# Battery.net
KiCad netlist of a schematic drawn in Altium Designer
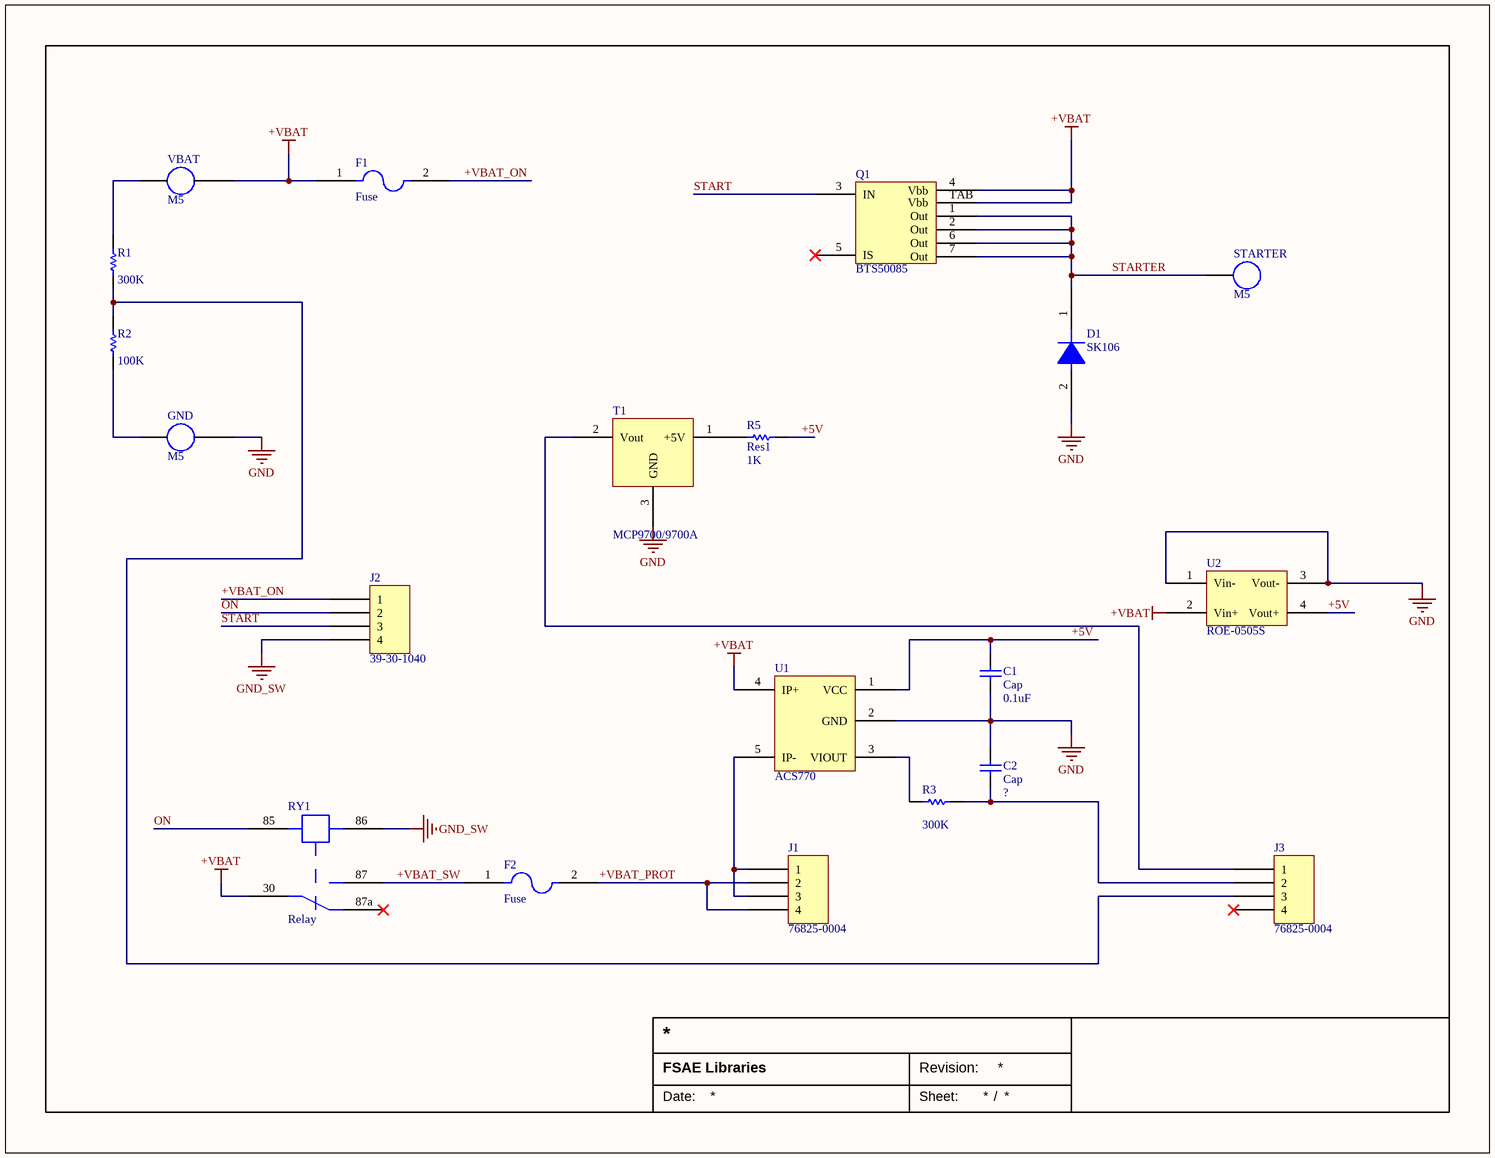
[diagram p0: Battery.SchDoc]

(export (version "E")
  (design (tool "Eeschema 10.0.6"))
  (components
    (comp (ref "C1")
      (value "Cap")
      (footprint "RAD-0.3")
      (description "Capacitor")
      (fields (field (name "ALTIUM_VALUE") "0.1uF") (field (name "PUBLISHER") "Altium Limited"))
      (libsource (lib "Miscellaneous Devices") (part "Cap"))
    )
    (comp (ref "C2")
      (value "Cap")
      (footprint "RAD-0.3")
      (description "Capacitor")
      (fields (field (name "ALTIUM_VALUE") "?") (field (name "PUBLISHER") "Altium Limited"))
      (libsource (lib "Miscellaneous Devices") (part "Cap"))
    )
    (comp (ref "D1") (value "SK106") (footprint "DIOM8060X54N") (libsource (lib "Battery") (part "SK106")))
    (comp (ref "F1") (value "Fuse") (footprint "FUSE") (libsource (lib "Battery") (part "Fuse")))
    (comp (ref "F2") (value "Fuse") (footprint "FUSE") (libsource (lib "Battery") (part "Fuse")))
    (comp (ref "GND")
      (value "M5")
      (footprint "MH-M5")
      (description "M5 mounting hole")
      (libsource (lib "Battery") (part "MH-M5"))
    )
    (comp (ref "J1")
      (value "76825-0004")
      (footprint "76825-0004")
      (libsource (lib "Connectors") (part "76825-0004"))
    )
    (comp (ref "J2")
      (value "39-30-1040")
      (footprint "39-30-1040")
      (libsource (lib "Connectors") (part "39-30-1040"))
    )
    (comp (ref "J3")
      (value "76825-0004")
      (footprint "76825-0004")
      (description "J3")
      (libsource (lib "Connectors") (part "76825-0004"))
    )
    (comp (ref "Q1") (value "BTS50085") (footprint "BTS50085") (libsource (lib "Battery") (part "BTS50085")))
    (comp (ref "R1")
      (value "~")
      (footprint "AXIAL-0.3")
      (description "Resistor")
      (fields (field (name "R1") "300K") (field (name "PUBLISHER") "Altium Limited"))
      (libsource (lib "Miscellaneous Devices") (part "Res1"))
    )
    (comp (ref "R2")
      (value "100K")
      (footprint "AXIAL-0.3")
      (description "Resistor")
      (fields (field (name "PUBLISHER") "Altium Limited"))
      (libsource (lib "Miscellaneous Devices") (part "Res1"))
    )
    (comp (ref "R3")
      (value "~")
      (footprint "AXIAL-0.3")
      (description "Resistor")
      (fields (field (name "R1") "300K") (field (name "PUBLISHER") "Altium Limited"))
      (libsource (lib "Miscellaneous Devices") (part "Res1"))
    )
    (comp (ref "R5")
      (value "Res1")
      (footprint "AXIAL-0.3")
      (description "Resistor")
      (fields (field (name "ALTIUM_VALUE") "1K") (field (name "PUBLISHER") "Altium Limited"))
      (libsource (lib "Miscellaneous Devices") (part "Res1"))
    )
    (comp (ref "RY1") (value "Relay") (footprint "Relay") (libsource (lib "Battery") (part "Relay")))
    (comp (ref "STARTER")
      (value "M5")
      (footprint "MH-M5")
      (description "M5 mounting hole")
      (libsource (lib "") (part "MH-M5_1"))
    )
    (comp (ref "T1")
      (value "MCP9700/9700A")
      (footprint "TempSensor")
      (description "Temp Sensor")
      (libsource (lib "Battery") (part "MCP9700/9700A"))
    )
    (comp (ref "U1") (value "ACS770") (footprint "ACS770") (libsource (lib "Battery") (part "ACS770")))
    (comp (ref "U2")
      (value "ROE-0505S")
      (footprint "ROE-0505S")
      (libsource (lib "Battery") (part "ROE-0505S"))
    )
    (comp (ref "VBAT")
      (value "M5")
      (footprint "MH-M5")
      (description "M5 mounting hole")
      (libsource (lib "Battery") (part "MH-M5"))
    )
  )
  (nets
    (net (code "1") (name "+VBAT") (class "Default")
      (node (ref "F1") (pin "1") (pinfunction "1_1") (pintype "passive"))
      (node (ref "Q1") (pin "4") (pinfunction "Vbb_4") (pintype "passive"))
      (node (ref "Q1") (pin "TAB") (pinfunction "Vbb_TAB") (pintype "passive"))
      (node (ref "RY1") (pin "30") (pinfunction "30_30") (pintype "passive"))
      (node (ref "U1") (pin "4") (pinfunction "IP+_4") (pintype "passive"))
      (node (ref "U2") (pin "2") (pinfunction "Vin+_2") (pintype "passive"))
    )
    (net (code "2") (name "/+5V") (class "Default")
      (node (ref "C1") (pin "1") (pinfunction "1_1") (pintype "passive"))
      (node (ref "R5") (pin "2") (pinfunction "2_2") (pintype "passive"))
      (node (ref "U1") (pin "1") (pinfunction "VCC_1") (pintype "passive"))
      (node (ref "U2") (pin "4") (pinfunction "Vout+_4") (pintype "passive"))
    )
    (net (code "3") (name "/+VBAT_ON") (class "Default")
      (node (ref "F1") (pin "2") (pinfunction "2_2") (pintype "passive"))
      (node (ref "J2") (pin "1") (pinfunction "1_1") (pintype "passive"))
    )
    (net (code "4") (name "/+VBAT_PROT") (class "Default")
      (node (ref "F2") (pin "2") (pinfunction "2_2") (pintype "passive"))
      (node (ref "J1") (pin "2") (pinfunction "2_2") (pintype "passive"))
      (node (ref "J1") (pin "4") (pinfunction "4_4") (pintype "passive"))
    )
    (net (code "5") (name "/+VBAT_SW") (class "Default")
      (node (ref "F2") (pin "1") (pinfunction "1_1") (pintype "passive"))
      (node (ref "RY1") (pin "87") (pinfunction "87_87") (pintype "passive"))
    )
    (net (code "6") (name "/ON") (class "Default")
      (node (ref "J2") (pin "2") (pinfunction "2_2") (pintype "passive"))
      (node (ref "RY1") (pin "85") (pinfunction "85_85") (pintype "passive"))
    )
    (net (code "7") (name "/START") (class "Default")
      (node (ref "J2") (pin "3") (pinfunction "3_3") (pintype "passive"))
      (node (ref "Q1") (pin "3") (pinfunction "IN_3") (pintype "passive"))
    )
    (net (code "8") (name "/STARTER") (class "Default")
      (node (ref "D1") (pin "1") (pinfunction "1_1") (pintype "passive"))
      (node (ref "Q1") (pin "1") (pinfunction "Out_1") (pintype "passive"))
      (node (ref "Q1") (pin "2") (pinfunction "Out_2") (pintype "passive"))
      (node (ref "Q1") (pin "6") (pinfunction "Out_6") (pintype "passive"))
      (node (ref "Q1") (pin "7") (pinfunction "Out_7") (pintype "passive"))
      (node (ref "STARTER") (pin "1") (pinfunction "1_1") (pintype "passive"))
    )
    (net (code "9") (name "GND") (class "Default")
      (node (ref "C1") (pin "2") (pinfunction "2_2") (pintype "passive"))
      (node (ref "C2") (pin "2") (pinfunction "2_2") (pintype "passive"))
      (node (ref "D1") (pin "2") (pinfunction "2_2") (pintype "passive"))
      (node (ref "T1") (pin "3") (pinfunction "GND_3") (pintype "passive"))
      (node (ref "U1") (pin "2") (pinfunction "GND_2") (pintype "passive"))
      (node (ref "U2") (pin "1") (pinfunction "Vin-_1") (pintype "passive"))
      (node (ref "U2") (pin "3") (pinfunction "Vout-_3") (pintype "passive"))
    )
    (net (code "10") (name "GND_SW") (class "Default")
      (node (ref "J2") (pin "4") (pinfunction "4_4") (pintype "passive"))
      (node (ref "RY1") (pin "86") (pinfunction "86_86") (pintype "passive"))
    )
    (net (code "11") (name "Net-(C2-Pad1)") (class "Default")
      (node (ref "C2") (pin "1") (pinfunction "1_1") (pintype "passive"))
      (node (ref "J3") (pin "2") (pinfunction "2_2") (pintype "passive"))
      (node (ref "R3") (pin "1") (pinfunction "1_1") (pintype "passive"))
    )
    (net (code "12") (name "Net-(GND-Pad1)") (class "Default")
      (node (ref "GND") (pin "1") (pinfunction "1_1") (pintype "passive"))
      (node (ref "R2") (pin "1") (pinfunction "1_1") (pintype "passive"))
    )
    (net (code "13") (name "Net-(J3-Pad3)") (class "Default")
      (node (ref "J3") (pin "3") (pinfunction "3_3") (pintype "passive"))
      (node (ref "R1") (pin "1") (pinfunction "1_1") (pintype "passive"))
      (node (ref "R2") (pin "2") (pinfunction "2_2") (pintype "passive"))
    )
    (net (code "14") (name "Net-(R1-Pad2)") (class "Default")
      (node (ref "R1") (pin "2") (pinfunction "2_2") (pintype "passive"))
      (node (ref "VBAT") (pin "1") (pinfunction "1_1") (pintype "passive"))
    )
    (net (code "15") (name "Net-(T1-+5V)") (class "Default")
      (node (ref "R5") (pin "1") (pinfunction "1_1") (pintype "passive"))
      (node (ref "T1") (pin "1") (pinfunction "+5V_1") (pintype "passive"))
    )
    (net (code "16") (name "Net-(T1-Vout)") (class "Default")
      (node (ref "J3") (pin "1") (pinfunction "1_1") (pintype "passive"))
      (node (ref "T1") (pin "2") (pinfunction "Vout_2") (pintype "passive"))
    )
    (net (code "17") (name "Net-(U1-IP-)") (class "Default")
      (node (ref "J1") (pin "1") (pinfunction "1_1") (pintype "passive"))
      (node (ref "J1") (pin "3") (pinfunction "3_3") (pintype "passive"))
      (node (ref "U1") (pin "5") (pinfunction "IP-_5") (pintype "passive"))
    )
    (net (code "18") (name "Net-(U1-VIOUT)") (class "Default")
      (node (ref "R3") (pin "2") (pinfunction "2_2") (pintype "passive"))
      (node (ref "U1") (pin "3") (pinfunction "VIOUT_3") (pintype "passive"))
    )
    (net (code "19") (name "unconnected-(GND-Pad)") (class "Default")
      (node (ref "GND") (pin "") (pintype "passive"))
    )
    (net (code "20") (name "unconnected-(J3-Pad4)") (class "Default")
      (node (ref "J3") (pin "4") (pinfunction "4_4") (pintype "passive+no_connect"))
    )
    (net (code "21") (name "unconnected-(Q1-IS-Pad5)") (class "Default")
      (node (ref "Q1") (pin "5") (pinfunction "IS_5") (pintype "passive+no_connect"))
    )
    (net (code "22") (name "unconnected-(RY1-Pad87a)") (class "Default")
      (node (ref "RY1") (pin "87a") (pinfunction "87a_87a") (pintype "passive+no_connect"))
    )
    (net (code "23") (name "unconnected-(VBAT-Pad)") (class "Default")
      (node (ref "VBAT") (pin "") (pintype "passive"))
    )
  )
)
